# Orthosie.net
KiCad netlist of a schematic drawn in EAGLE
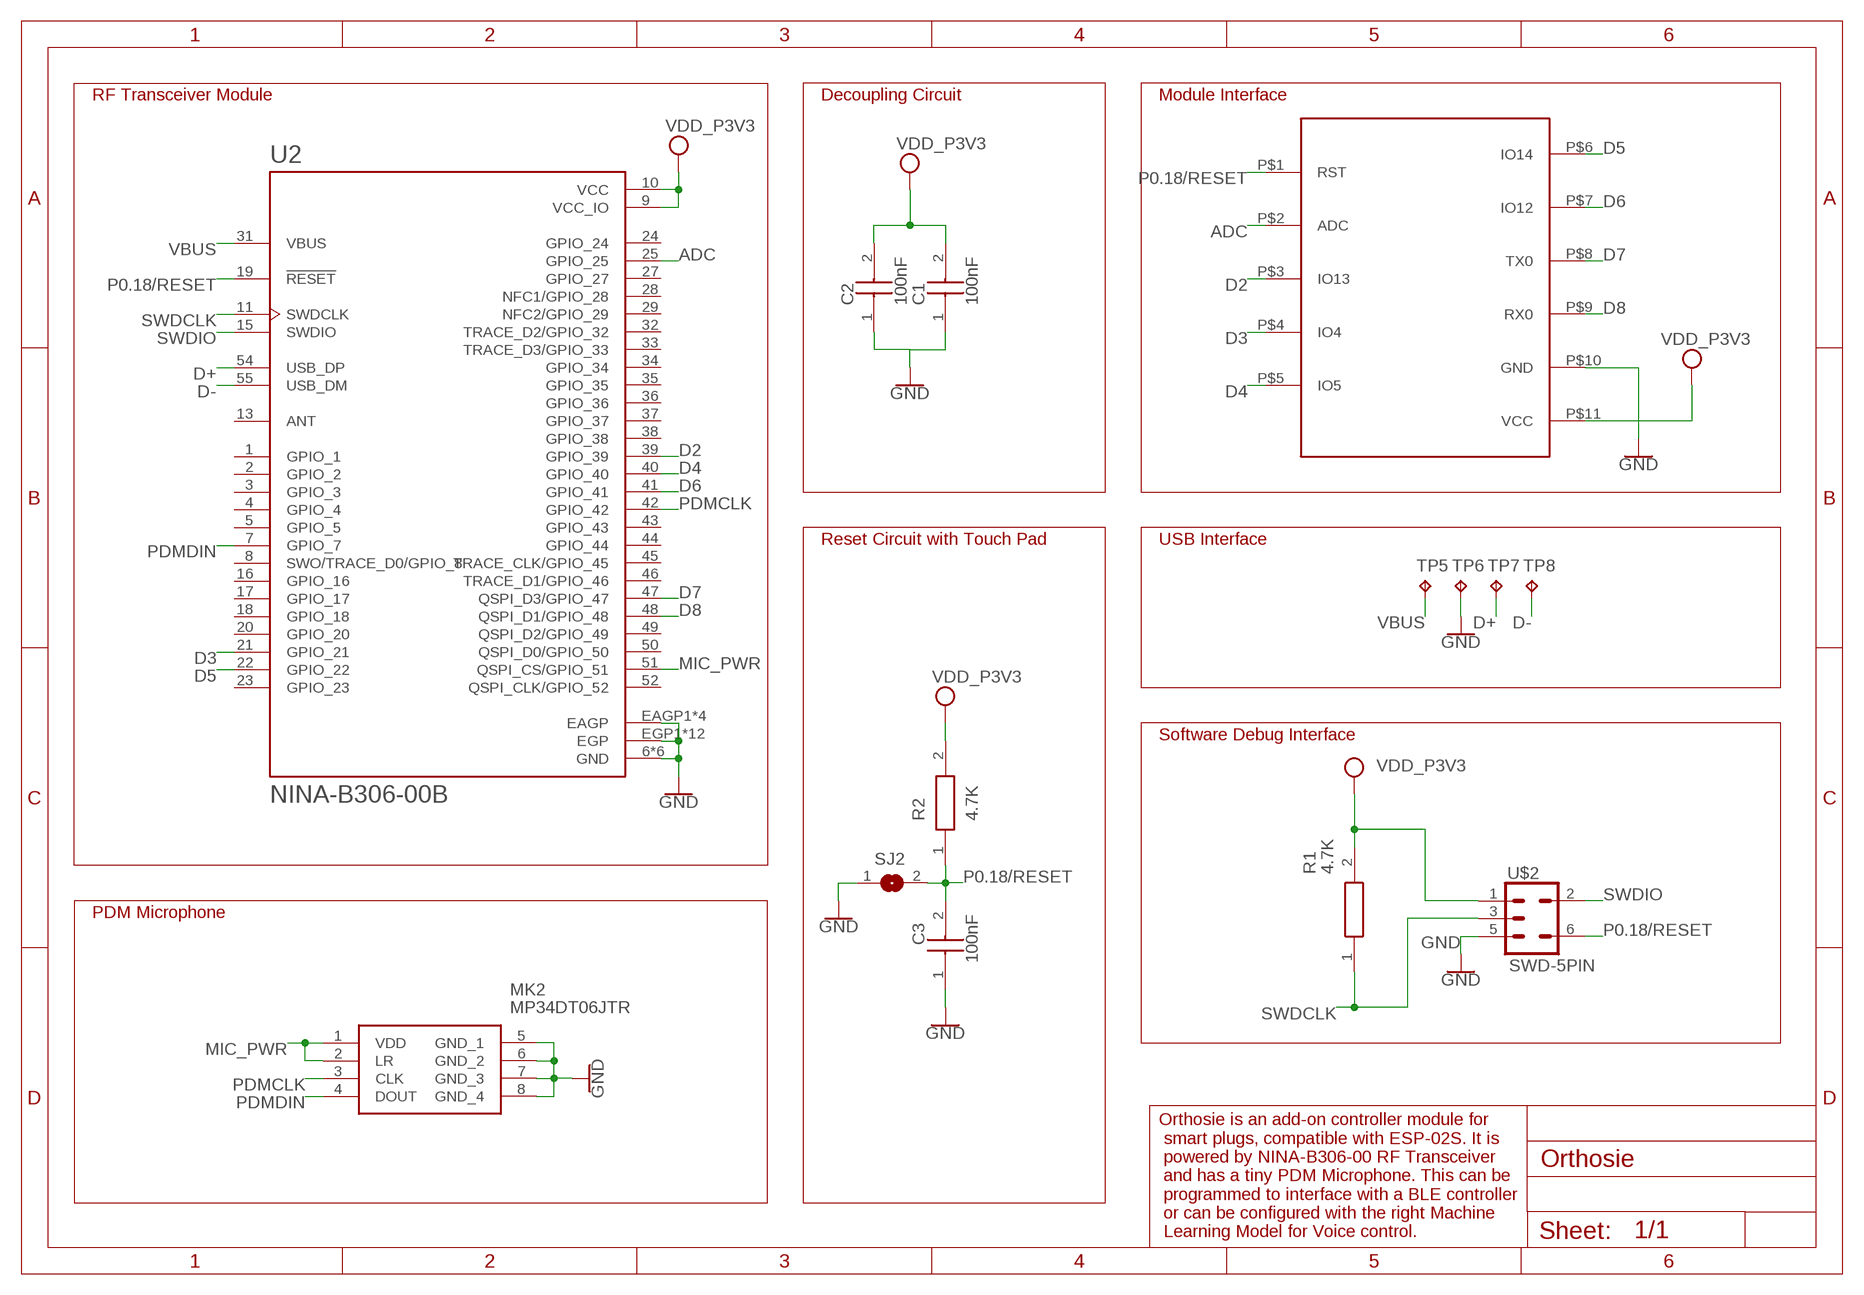
[diagram p0: schematic, sheet 1]

(export (version "E")
  (design (tool "Eeschema 10.0.6"))
  (components
    (comp (ref "C1")
      (value "100nF")
      (footprint "eagle-import:CAPC1005X55N")
      (fields
        (field (name "MANUFACTURER_PART_NUMBER") "GJM1555C1H120JB01J")
        (field (name "MOUSER_PART_NUMBER") "81-GJM1555C1H120JB1J")
      )
      (libsource (lib "eagle-import") (part "GJM1555C1H120JB01J"))
    )
    (comp (ref "C2")
      (value "100nF")
      (footprint "eagle-import:CAPC1005X55N")
      (fields
        (field (name "MANUFACTURER_PART_NUMBER") "GJM1555C1H120JB01J")
        (field (name "MOUSER_PART_NUMBER") "81-GJM1555C1H120JB1J")
      )
      (libsource (lib "eagle-import") (part "GJM1555C1H120JB01J"))
    )
    (comp (ref "C3")
      (value "100nF")
      (footprint "eagle-import:CAPC1005X55N")
      (fields
        (field (name "MANUFACTURER_PART_NUMBER") "GJM1555C1H120JB01J")
        (field (name "MOUSER_PART_NUMBER") "81-GJM1555C1H120JB1J")
      )
      (libsource (lib "eagle-import") (part "GJM1555C1H120JB01J"))
    )
    (comp (ref "MK2")
      (value "MP34DT06JTR")
      (footprint "eagle-import:MP34DT06JTR")
      (fields (field (name "MOUSER_PART_NUMBER") "511-MP34DT06JTR"))
      (libsource (lib "eagle-import") (part "MP34DT06JTR"))
    )
    (comp (ref "R1")
      (value "4.7K")
      (footprint "eagle-import:RESC1005X40N")
      (fields
        (field (name "ARROW_PART_NUMBER") "CRCW04020000Z0EE")
        (field (name "MOUSER_PART_NUMBER") "71-CRCW04020000Z0EE")
      )
      (libsource (lib "eagle-import") (part "CRCW04020000Z0EE"))
    )
    (comp (ref "R2")
      (value "4.7K")
      (footprint "eagle-import:RESC1005X40N")
      (fields
        (field (name "ARROW_PART_NUMBER") "CRCW04020000Z0EE")
        (field (name "MOUSER_PART_NUMBER") "71-CRCW04020000Z0EE")
      )
      (libsource (lib "eagle-import") (part "CRCW04020000Z0EE"))
    )
    (comp (ref "SJ2") (value "SJ") (footprint "eagle-import:SJ") (libsource (lib "eagle-import") (part "SJ")))
    (comp (ref "TP5")
      (value "TPB1,27")
      (footprint "eagle-import:B1,27")
      (libsource (lib "eagle-import") (part "TPB1,27"))
    )
    (comp (ref "TP6")
      (value "TPB1,27")
      (footprint "eagle-import:B1,27")
      (libsource (lib "eagle-import") (part "TPB1,27"))
    )
    (comp (ref "TP7")
      (value "TPB1,27")
      (footprint "eagle-import:B1,27")
      (libsource (lib "eagle-import") (part "TPB1,27"))
    )
    (comp (ref "TP8")
      (value "TPB1,27")
      (footprint "eagle-import:B1,27")
      (libsource (lib "eagle-import") (part "TPB1,27"))
    )
    (comp (ref "U$1")
      (value "ESP02SESP02S_MIRROR")
      (footprint "eagle-import:ESP02S_MIRROR")
      (libsource (lib "eagle-import") (part "ESP02SESP02S_MIRROR"))
    )
    (comp (ref "U$2")
      (value "SWD-5PIN")
      (footprint "eagle-import:PAD_05_03X2_TP_NO4")
      (libsource (lib "eagle-import") (part "SWD-5PIN"))
    )
    (comp (ref "U2")
      (value "NINA-B306-00B")
      (footprint "eagle-import:XCVR_NINA-B306-00B")
      (fields (field (name "MF") "U-Blox"))
      (libsource (lib "eagle-import") (part "NINA-B306-00B"))
    )
  )
  (nets
    (net (code "1") (name "/ADC") (class "Default")
      (node (ref "U$1") (pin "P$2") (pinfunction "ADC_P$2") (pintype "input"))
      (node (ref "U2") (pin "25") (pinfunction "GPIO_25_25") (pintype "bidirectional"))
    )
    (net (code "2") (name "/D+") (class "Default")
      (node (ref "TP7") (pin "TP") (pinfunction "TP_TP") (pintype "input"))
      (node (ref "U2") (pin "54") (pinfunction "USB_DP_54") (pintype "bidirectional"))
    )
    (net (code "3") (name "/D-") (class "Default")
      (node (ref "TP8") (pin "TP") (pinfunction "TP_TP") (pintype "input"))
      (node (ref "U2") (pin "55") (pinfunction "USB_DM_55") (pintype "bidirectional"))
    )
    (net (code "4") (name "/D2") (class "Default")
      (node (ref "U$1") (pin "P$3") (pinfunction "IO13_P$3") (pintype "bidirectional"))
      (node (ref "U2") (pin "39") (pinfunction "GPIO_39_39") (pintype "bidirectional"))
    )
    (net (code "5") (name "/D3") (class "Default")
      (node (ref "U$1") (pin "P$4") (pinfunction "IO4_P$4") (pintype "bidirectional"))
      (node (ref "U2") (pin "21") (pinfunction "GPIO_21_21") (pintype "bidirectional"))
    )
    (net (code "6") (name "/D4") (class "Default")
      (node (ref "U$1") (pin "P$5") (pinfunction "IO5_P$5") (pintype "bidirectional"))
      (node (ref "U2") (pin "40") (pinfunction "GPIO_40_40") (pintype "bidirectional"))
    )
    (net (code "7") (name "/D5") (class "Default")
      (node (ref "U$1") (pin "P$6") (pinfunction "IO14_P$6") (pintype "bidirectional"))
      (node (ref "U2") (pin "22") (pinfunction "GPIO_22_22") (pintype "bidirectional"))
    )
    (net (code "8") (name "/D6") (class "Default")
      (node (ref "U$1") (pin "P$7") (pinfunction "IO12_P$7") (pintype "bidirectional"))
      (node (ref "U2") (pin "41") (pinfunction "GPIO_41_41") (pintype "bidirectional"))
    )
    (net (code "9") (name "/D7") (class "Default")
      (node (ref "U$1") (pin "P$8") (pinfunction "TX0_P$8") (pintype "output"))
      (node (ref "U2") (pin "47") (pinfunction "QSPI_D3/GPIO_47_47") (pintype "bidirectional"))
    )
    (net (code "10") (name "/D8") (class "Default")
      (node (ref "U$1") (pin "P$9") (pinfunction "RX0_P$9") (pintype "input"))
      (node (ref "U2") (pin "48") (pinfunction "QSPI_D1/GPIO_48_48") (pintype "bidirectional"))
    )
    (net (code "11") (name "/MIC_PWR") (class "Default")
      (node (ref "MK2") (pin "1") (pinfunction "VDD_1") (pintype "bidirectional"))
      (node (ref "MK2") (pin "2") (pinfunction "LR_2") (pintype "bidirectional"))
      (node (ref "U2") (pin "51") (pinfunction "QSPI_CS/GPIO_51_51") (pintype "bidirectional"))
    )
    (net (code "12") (name "/P0.18{slash}RESET") (class "Default")
      (node (ref "C3") (pin "2") (pinfunction "2_2") (pintype "bidirectional"))
      (node (ref "R2") (pin "1") (pinfunction "1_1") (pintype "bidirectional"))
      (node (ref "SJ2") (pin "2") (pinfunction "2_2") (pintype "passive"))
      (node (ref "U$1") (pin "P$1") (pinfunction "RST_P$1") (pintype "input"))
      (node (ref "U$2") (pin "6") (pinfunction "6_6") (pintype "bidirectional"))
      (node (ref "U2") (pin "19") (pinfunction "~{RESET}_19") (pintype "bidirectional"))
    )
    (net (code "13") (name "/PDMCLK") (class "Default")
      (node (ref "MK2") (pin "3") (pinfunction "CLK_3") (pintype "bidirectional"))
      (node (ref "U2") (pin "42") (pinfunction "GPIO_42_42") (pintype "bidirectional"))
    )
    (net (code "14") (name "/PDMDIN") (class "Default")
      (node (ref "MK2") (pin "4") (pinfunction "DOUT_4") (pintype "bidirectional"))
      (node (ref "U2") (pin "7") (pinfunction "GPIO_7_7") (pintype "bidirectional"))
    )
    (net (code "15") (name "/SWDCLK") (class "Default")
      (node (ref "R1") (pin "1") (pinfunction "1_1") (pintype "bidirectional"))
      (node (ref "U$2") (pin "3") (pinfunction "3_3") (pintype "bidirectional"))
      (node (ref "U2") (pin "11") (pinfunction "SWDCLK_11") (pintype "input"))
    )
    (net (code "16") (name "/SWDIO") (class "Default")
      (node (ref "U$2") (pin "2") (pinfunction "2_2") (pintype "bidirectional"))
      (node (ref "U2") (pin "15") (pinfunction "SWDIO_15") (pintype "bidirectional"))
    )
    (net (code "17") (name "/VBUS") (class "Default")
      (node (ref "TP5") (pin "TP") (pinfunction "TP_TP") (pintype "input"))
      (node (ref "U2") (pin "31") (pinfunction "VBUS_31") (pintype "input"))
    )
    (net (code "18") (name "GND") (class "Default")
      (node (ref "C1") (pin "1") (pinfunction "1_1") (pintype "bidirectional"))
      (node (ref "C2") (pin "1") (pinfunction "1_1") (pintype "bidirectional"))
      (node (ref "C3") (pin "1") (pinfunction "1_1") (pintype "bidirectional"))
      (node (ref "MK2") (pin "5") (pinfunction "GND_1_5") (pintype "bidirectional"))
      (node (ref "MK2") (pin "6") (pinfunction "GND_2_6") (pintype "bidirectional"))
      (node (ref "MK2") (pin "7") (pinfunction "GND_3_7") (pintype "bidirectional"))
      (node (ref "MK2") (pin "8") (pinfunction "GND_4_8") (pintype "bidirectional"))
      (node (ref "SJ2") (pin "1") (pinfunction "1_1") (pintype "passive"))
      (node (ref "TP6") (pin "TP") (pinfunction "TP_TP") (pintype "input"))
      (node (ref "U$1") (pin "P$10") (pinfunction "GND_P$10") (pintype "power_in"))
      (node (ref "U$2") (pin "5") (pinfunction "5_5") (pintype "bidirectional"))
      (node (ref "U2") (pin "12") (pinfunction "GND_12") (pintype "power_in"))
      (node (ref "U2") (pin "14") (pinfunction "GND_14") (pintype "power_in"))
      (node (ref "U2") (pin "26") (pinfunction "GND_26") (pintype "power_in"))
      (node (ref "U2") (pin "30") (pinfunction "GND_30") (pintype "power_in"))
      (node (ref "U2") (pin "53") (pinfunction "GND_53") (pintype "power_in"))
      (node (ref "U2") (pin "6") (pinfunction "GND_6") (pintype "power_in"))
      (node (ref "U2") (pin "EAGP1") (pinfunction "EAGP_EAGP1") (pintype "power_in"))
      (node (ref "U2") (pin "EAGP2") (pinfunction "EAGP_EAGP2") (pintype "power_in"))
      (node (ref "U2") (pin "EAGP3") (pinfunction "EAGP_EAGP3") (pintype "power_in"))
      (node (ref "U2") (pin "EAGP4") (pinfunction "EAGP_EAGP4") (pintype "power_in"))
      (node (ref "U2") (pin "EGP1") (pinfunction "EGP_EGP1") (pintype "power_in"))
      (node (ref "U2") (pin "EGP10") (pinfunction "EGP_EGP10") (pintype "power_in"))
      (node (ref "U2") (pin "EGP11") (pinfunction "EGP_EGP11") (pintype "power_in"))
      (node (ref "U2") (pin "EGP12") (pinfunction "EGP_EGP12") (pintype "power_in"))
      (node (ref "U2") (pin "EGP2") (pinfunction "EGP_EGP2") (pintype "power_in"))
      (node (ref "U2") (pin "EGP3") (pinfunction "EGP_EGP3") (pintype "power_in"))
      (node (ref "U2") (pin "EGP4") (pinfunction "EGP_EGP4") (pintype "power_in"))
      (node (ref "U2") (pin "EGP5") (pinfunction "EGP_EGP5") (pintype "power_in"))
      (node (ref "U2") (pin "EGP6") (pinfunction "EGP_EGP6") (pintype "power_in"))
      (node (ref "U2") (pin "EGP7") (pinfunction "EGP_EGP7") (pintype "power_in"))
      (node (ref "U2") (pin "EGP8") (pinfunction "EGP_EGP8") (pintype "power_in"))
      (node (ref "U2") (pin "EGP9") (pinfunction "EGP_EGP9") (pintype "power_in"))
    )
    (net (code "19") (name "VDD_P3V3") (class "Default")
      (node (ref "C1") (pin "2") (pinfunction "2_2") (pintype "bidirectional"))
      (node (ref "C2") (pin "2") (pinfunction "2_2") (pintype "bidirectional"))
      (node (ref "R1") (pin "2") (pinfunction "2_2") (pintype "bidirectional"))
      (node (ref "R2") (pin "2") (pinfunction "2_2") (pintype "bidirectional"))
      (node (ref "U$1") (pin "P$11") (pinfunction "VCC_P$11") (pintype "power_in"))
      (node (ref "U$2") (pin "1") (pinfunction "1_1") (pintype "bidirectional"))
      (node (ref "U2") (pin "10") (pinfunction "VCC_10") (pintype "power_in"))
      (node (ref "U2") (pin "9") (pinfunction "VCC_IO_9") (pintype "power_in"))
    )
    (net (code "20") (name "unconnected-(U2-ANT-Pad13)") (class "Default")
      (node (ref "U2") (pin "13") (pinfunction "ANT_13") (pintype "bidirectional"))
    )
    (net (code "21") (name "unconnected-(U2-GPIO_1-Pad1)") (class "Default")
      (node (ref "U2") (pin "1") (pinfunction "GPIO_1_1") (pintype "bidirectional"))
    )
    (net (code "22") (name "unconnected-(U2-GPIO_2-Pad2)") (class "Default")
      (node (ref "U2") (pin "2") (pinfunction "GPIO_2_2") (pintype "bidirectional"))
    )
    (net (code "23") (name "unconnected-(U2-GPIO_3-Pad3)") (class "Default")
      (node (ref "U2") (pin "3") (pinfunction "GPIO_3_3") (pintype "bidirectional"))
    )
    (net (code "24") (name "unconnected-(U2-GPIO_4-Pad4)") (class "Default")
      (node (ref "U2") (pin "4") (pinfunction "GPIO_4_4") (pintype "bidirectional"))
    )
    (net (code "25") (name "unconnected-(U2-GPIO_5-Pad5)") (class "Default")
      (node (ref "U2") (pin "5") (pinfunction "GPIO_5_5") (pintype "bidirectional"))
    )
    (net (code "26") (name "unconnected-(U2-GPIO_16-Pad16)") (class "Default")
      (node (ref "U2") (pin "16") (pinfunction "GPIO_16_16") (pintype "bidirectional"))
    )
    (net (code "27") (name "unconnected-(U2-GPIO_17-Pad17)") (class "Default")
      (node (ref "U2") (pin "17") (pinfunction "GPIO_17_17") (pintype "bidirectional"))
    )
    (net (code "28") (name "unconnected-(U2-GPIO_18-Pad18)") (class "Default")
      (node (ref "U2") (pin "18") (pinfunction "GPIO_18_18") (pintype "bidirectional"))
    )
    (net (code "29") (name "unconnected-(U2-GPIO_20-Pad20)") (class "Default")
      (node (ref "U2") (pin "20") (pinfunction "GPIO_20_20") (pintype "bidirectional"))
    )
    (net (code "30") (name "unconnected-(U2-GPIO_23-Pad23)") (class "Default")
      (node (ref "U2") (pin "23") (pinfunction "GPIO_23_23") (pintype "bidirectional"))
    )
    (net (code "31") (name "unconnected-(U2-GPIO_24-Pad24)") (class "Default")
      (node (ref "U2") (pin "24") (pinfunction "GPIO_24_24") (pintype "bidirectional"))
    )
    (net (code "32") (name "unconnected-(U2-GPIO_27-Pad27)") (class "Default")
      (node (ref "U2") (pin "27") (pinfunction "GPIO_27_27") (pintype "bidirectional"))
    )
    (net (code "33") (name "unconnected-(U2-GPIO_34-Pad34)") (class "Default")
      (node (ref "U2") (pin "34") (pinfunction "GPIO_34_34") (pintype "bidirectional"))
    )
    (net (code "34") (name "unconnected-(U2-GPIO_35-Pad35)") (class "Default")
      (node (ref "U2") (pin "35") (pinfunction "GPIO_35_35") (pintype "bidirectional"))
    )
    (net (code "35") (name "unconnected-(U2-GPIO_36-Pad36)") (class "Default")
      (node (ref "U2") (pin "36") (pinfunction "GPIO_36_36") (pintype "bidirectional"))
    )
    (net (code "36") (name "unconnected-(U2-GPIO_37-Pad37)") (class "Default")
      (node (ref "U2") (pin "37") (pinfunction "GPIO_37_37") (pintype "bidirectional"))
    )
    (net (code "37") (name "unconnected-(U2-GPIO_38-Pad38)") (class "Default")
      (node (ref "U2") (pin "38") (pinfunction "GPIO_38_38") (pintype "bidirectional"))
    )
    (net (code "38") (name "unconnected-(U2-GPIO_43-Pad43)") (class "Default")
      (node (ref "U2") (pin "43") (pinfunction "GPIO_43_43") (pintype "bidirectional"))
    )
    (net (code "39") (name "unconnected-(U2-GPIO_44-Pad44)") (class "Default")
      (node (ref "U2") (pin "44") (pinfunction "GPIO_44_44") (pintype "bidirectional"))
    )
    (net (code "40") (name "unconnected-(U2-NFC1{slash}GPIO_28-Pad28)") (class "Default")
      (node (ref "U2") (pin "28") (pinfunction "NFC1/GPIO_28_28") (pintype "bidirectional"))
    )
    (net (code "41") (name "unconnected-(U2-NFC2{slash}GPIO_29-Pad29)") (class "Default")
      (node (ref "U2") (pin "29") (pinfunction "NFC2/GPIO_29_29") (pintype "bidirectional"))
    )
    (net (code "42") (name "unconnected-(U2-QSPI_CLK{slash}GPIO_52-Pad52)") (class "Default")
      (node (ref "U2") (pin "52") (pinfunction "QSPI_CLK/GPIO_52_52") (pintype "bidirectional"))
    )
    (net (code "43") (name "unconnected-(U2-QSPI_D0{slash}GPIO_50-Pad50)") (class "Default")
      (node (ref "U2") (pin "50") (pinfunction "QSPI_D0/GPIO_50_50") (pintype "bidirectional"))
    )
    (net (code "44") (name "unconnected-(U2-QSPI_D2{slash}GPIO_49-Pad49)") (class "Default")
      (node (ref "U2") (pin "49") (pinfunction "QSPI_D2/GPIO_49_49") (pintype "bidirectional"))
    )
    (net (code "45") (name "unconnected-(U2-SWO{slash}TRACE_D0{slash}GPIO_8-Pad8)") (class "Default")
      (node (ref "U2") (pin "8") (pinfunction "SWO/TRACE_D0/GPIO_8_8") (pintype "bidirectional"))
    )
    (net (code "46") (name "unconnected-(U2-TRACE_CLK{slash}GPIO_45-Pad45)") (class "Default")
      (node (ref "U2") (pin "45") (pinfunction "TRACE_CLK/GPIO_45_45") (pintype "bidirectional"))
    )
    (net (code "47") (name "unconnected-(U2-TRACE_D1{slash}GPIO_46-Pad46)") (class "Default")
      (node (ref "U2") (pin "46") (pinfunction "TRACE_D1/GPIO_46_46") (pintype "bidirectional"))
    )
    (net (code "48") (name "unconnected-(U2-TRACE_D2{slash}GPIO_32-Pad32)") (class "Default")
      (node (ref "U2") (pin "32") (pinfunction "TRACE_D2/GPIO_32_32") (pintype "bidirectional"))
    )
    (net (code "49") (name "unconnected-(U2-TRACE_D3{slash}GPIO_33-Pad33)") (class "Default")
      (node (ref "U2") (pin "33") (pinfunction "TRACE_D3/GPIO_33_33") (pintype "bidirectional"))
    )
  )
)
